# waterlevel.net
KiCad netlist of a schematic drawn in EAGLE
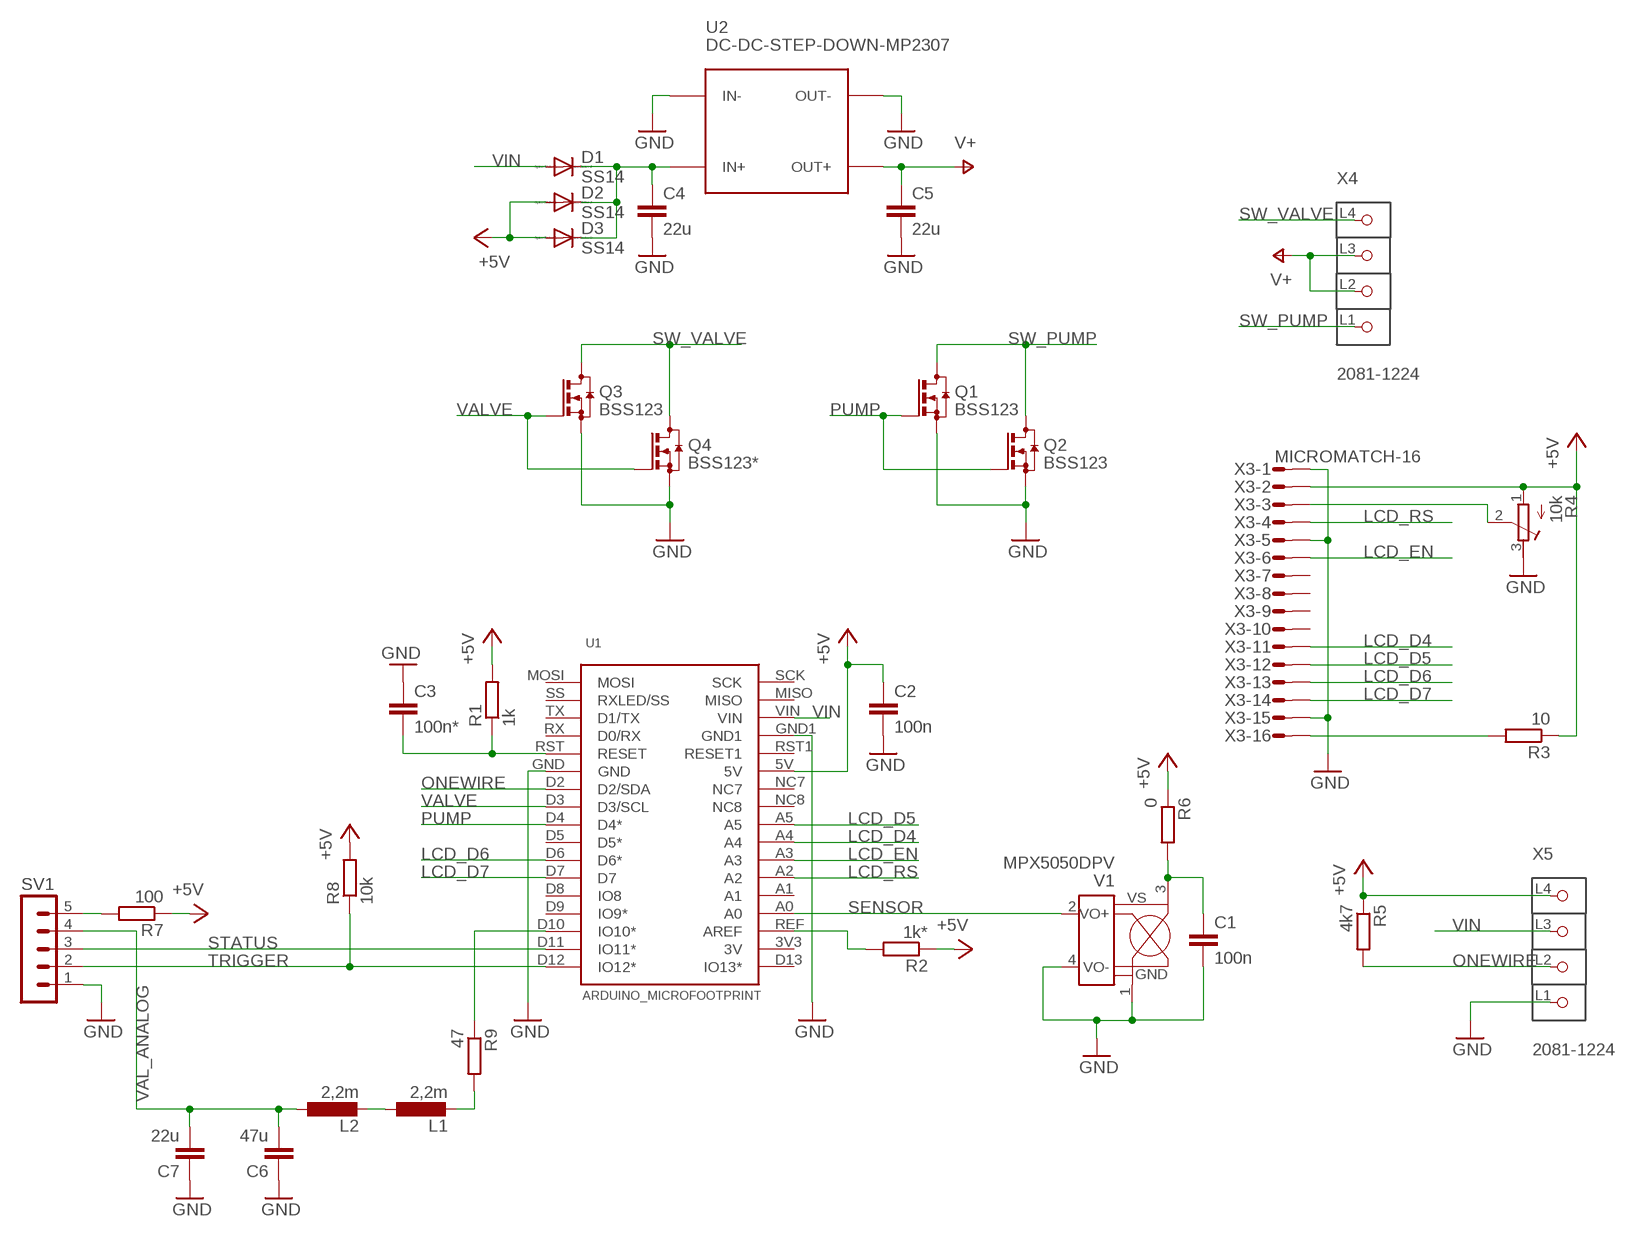
[diagram p0: schematic, sheet 1]

(export (version "E")
  (design (tool "Eeschema 10.0.6"))
  (components
    (comp (ref "C1")
      (value "100n")
      (footprint "eagle-import:C0603")
      (libsource (lib "eagle-import") (part "C-EUC0603"))
    )
    (comp (ref "C2")
      (value "100n")
      (footprint "eagle-import:C0603")
      (libsource (lib "eagle-import") (part "C-EUC0603"))
    )
    (comp (ref "C3")
      (value "100n*")
      (footprint "eagle-import:C0603")
      (libsource (lib "eagle-import") (part "C-EUC0603"))
    )
    (comp (ref "C4")
      (value "22u")
      (footprint "eagle-import:C1210K")
      (libsource (lib "eagle-import") (part "C-EUC1210K"))
    )
    (comp (ref "C5")
      (value "22u")
      (footprint "eagle-import:C1210K")
      (libsource (lib "eagle-import") (part "C-EUC1210K"))
    )
    (comp (ref "C6")
      (value "47u")
      (footprint "eagle-import:C1206K")
      (libsource (lib "eagle-import") (part "C-EUC1206K"))
    )
    (comp (ref "C7")
      (value "22u")
      (footprint "eagle-import:C1206K")
      (libsource (lib "eagle-import") (part "C-EUC1206K"))
    )
    (comp (ref "D1")
      (value "SS14")
      (footprint "eagle-import:DO214AC")
      (libsource (lib "eagle-import") (part "DIODE-DO214AC"))
    )
    (comp (ref "D2")
      (value "SS14")
      (footprint "eagle-import:DO214AC")
      (libsource (lib "eagle-import") (part "DIODE-DO214AC"))
    )
    (comp (ref "D3")
      (value "SS14")
      (footprint "eagle-import:DO214AC")
      (libsource (lib "eagle-import") (part "DIODE-DO214AC"))
    )
    (comp (ref "L1")
      (value "2,2m")
      (footprint "eagle-import:L1812")
      (libsource (lib "eagle-import") (part "L-EUL1812"))
    )
    (comp (ref "L2")
      (value "2,2m")
      (footprint "eagle-import:L1812")
      (libsource (lib "eagle-import") (part "L-EUL1812"))
    )
    (comp (ref "Q1")
      (value "BSS123")
      (footprint "eagle-import:SOT23")
      (libsource (lib "eagle-import") (part "BSS123"))
    )
    (comp (ref "Q2")
      (value "BSS123")
      (footprint "eagle-import:SOT23")
      (libsource (lib "eagle-import") (part "BSS123"))
    )
    (comp (ref "Q3")
      (value "BSS123")
      (footprint "eagle-import:SOT23")
      (libsource (lib "eagle-import") (part "BSS123"))
    )
    (comp (ref "Q4")
      (value "BSS123*")
      (footprint "eagle-import:SOT23")
      (libsource (lib "eagle-import") (part "BSS123"))
    )
    (comp (ref "R1")
      (value "1k")
      (footprint "eagle-import:R0603")
      (libsource (lib "eagle-import") (part "R-EU_R0603"))
    )
    (comp (ref "R2")
      (value "1k*")
      (footprint "eagle-import:R0603")
      (libsource (lib "eagle-import") (part "R-EU_R0603"))
    )
    (comp (ref "R3")
      (value "10")
      (footprint "eagle-import:R0603")
      (libsource (lib "eagle-import") (part "R-EU_R0603"))
    )
    (comp (ref "R4")
      (value "10k")
      (footprint "eagle-import:RTRIM64Z")
      (libsource (lib "eagle-import") (part "R-TRIMM64Z"))
    )
    (comp (ref "R5")
      (value "4k7")
      (footprint "eagle-import:R0603")
      (libsource (lib "eagle-import") (part "R-EU_R0603"))
    )
    (comp (ref "R6")
      (value "0")
      (footprint "eagle-import:R0603")
      (libsource (lib "eagle-import") (part "R-EU_R0603"))
    )
    (comp (ref "R7")
      (value "100")
      (footprint "eagle-import:R0603")
      (libsource (lib "eagle-import") (part "R-EU_R0603"))
    )
    (comp (ref "R8")
      (value "10k")
      (footprint "eagle-import:R0603")
      (libsource (lib "eagle-import") (part "R-EU_R0603"))
    )
    (comp (ref "R9")
      (value "47")
      (footprint "eagle-import:R0603")
      (libsource (lib "eagle-import") (part "R-EU_R0603"))
    )
    (comp (ref "SV1")
      (value "MA05-1")
      (footprint "eagle-import:MA05-1")
      (libsource (lib "eagle-import") (part "MA05-1"))
    )
    (comp (ref "U1")
      (value "ARDUINO_MICROFOOTPRINT")
      (footprint "eagle-import:ARDUINO-MICRO")
      (libsource (lib "eagle-import") (part "ARDUINO_MICROFOOTPRINT"))
    )
    (comp (ref "U2")
      (value "DC-DC-STEP-DOWN-MP2307")
      (footprint "eagle-import:DC-DC-STEP-DOWN-MP2307")
      (libsource (lib "eagle-import") (part "DC-DC-STEP-DOWN-MP2307"))
    )
    (comp (ref "V1")
      (value "MPX5050DPV")
      (footprint "eagle-import:MPX2050DPV")
      (fields (field (name "MF") "MOTOROLA") (field (name "MPN") "MPX2050DP"))
      (libsource (lib "eagle-import") (part "MPX2050DPV"))
    )
    (comp (ref "X3")
      (value "MICROMATCH-16")
      (footprint "eagle-import:MICROMATCH-16")
      (fields (field (name "MF") "FARNELL") (field (name "MPN") "8-215464-6"))
      (libsource (lib "eagle-import") (part "MICROMATCH-16"))
    )
    (comp (ref "X4")
      (value "2081-1224")
      (footprint "eagle-import:P-2081-1224")
      (libsource (lib "eagle-import") (part "2081-1224"))
    )
    (comp (ref "X5")
      (value "2081-1224")
      (footprint "eagle-import:P-2081-1224")
      (libsource (lib "eagle-import") (part "2081-1224"))
    )
  )
  (nets
    (net (code "1") (name "+5V") (class "Default")
      (node (ref "C2") (pin "1") (pinfunction "1_1") (pintype "passive"))
      (node (ref "D2") (pin "A") (pinfunction "A_A") (pintype "passive"))
      (node (ref "D3") (pin "A") (pinfunction "A_A") (pintype "passive"))
      (node (ref "R1") (pin "2") (pinfunction "2_2") (pintype "passive"))
      (node (ref "R2") (pin "1") (pinfunction "1_1") (pintype "passive"))
      (node (ref "R3") (pin "1") (pinfunction "1_1") (pintype "passive"))
      (node (ref "R4") (pin "1") (pinfunction "A_1") (pintype "passive"))
      (node (ref "R5") (pin "1") (pinfunction "1_1") (pintype "passive"))
      (node (ref "R6") (pin "1") (pinfunction "1_1") (pintype "passive"))
      (node (ref "R7") (pin "1") (pinfunction "1_1") (pintype "passive"))
      (node (ref "R8") (pin "2") (pinfunction "2_2") (pintype "passive"))
      (node (ref "U1") (pin "5V") (pinfunction "5V_5V") (pintype "bidirectional"))
      (node (ref "X3") (pin "2") (pinfunction "S_2") (pintype "passive"))
      (node (ref "X5") (pin "L4") (pinfunction "P4_L4") (pintype "bidirectional"))
    )
    (net (code "2") (name "/LCD_D4") (class "Default")
      (node (ref "U1") (pin "A4") (pinfunction "A4_A4") (pintype "bidirectional"))
      (node (ref "X3") (pin "11") (pinfunction "S_11") (pintype "passive"))
    )
    (net (code "3") (name "/LCD_D5") (class "Default")
      (node (ref "U1") (pin "A5") (pinfunction "A5_A5") (pintype "bidirectional"))
      (node (ref "X3") (pin "12") (pinfunction "S_12") (pintype "passive"))
    )
    (net (code "4") (name "/LCD_D6") (class "Default")
      (node (ref "U1") (pin "D6") (pinfunction "D6*_D6") (pintype "bidirectional"))
      (node (ref "X3") (pin "13") (pinfunction "S_13") (pintype "passive"))
    )
    (net (code "5") (name "/LCD_D7") (class "Default")
      (node (ref "U1") (pin "D7") (pinfunction "D7_D7") (pintype "bidirectional"))
      (node (ref "X3") (pin "14") (pinfunction "S_14") (pintype "passive"))
    )
    (net (code "6") (name "/LCD_EN") (class "Default")
      (node (ref "U1") (pin "A3") (pinfunction "A3_A3") (pintype "bidirectional"))
      (node (ref "X3") (pin "6") (pinfunction "S_6") (pintype "passive"))
    )
    (net (code "7") (name "/LCD_RS") (class "Default")
      (node (ref "U1") (pin "A2") (pinfunction "A2_A2") (pintype "bidirectional"))
      (node (ref "X3") (pin "4") (pinfunction "S_4") (pintype "passive"))
    )
    (net (code "8") (name "/ONEWIRE") (class "Default")
      (node (ref "R5") (pin "2") (pinfunction "2_2") (pintype "passive"))
      (node (ref "U1") (pin "D2") (pinfunction "D2/SDA_D2") (pintype "bidirectional"))
      (node (ref "X5") (pin "L2") (pinfunction "P2_L2") (pintype "bidirectional"))
    )
    (net (code "9") (name "/PUMP") (class "Default")
      (node (ref "Q1") (pin "1") (pinfunction "G_1") (pintype "passive"))
      (node (ref "Q2") (pin "1") (pinfunction "G_1") (pintype "passive"))
      (node (ref "U1") (pin "D4") (pinfunction "D4*_D4") (pintype "bidirectional"))
    )
    (net (code "10") (name "/SENSOR") (class "Default")
      (node (ref "U1") (pin "A0") (pinfunction "A0_A0") (pintype "bidirectional"))
      (node (ref "V1") (pin "2") (pinfunction "VO+_2") (pintype "passive"))
    )
    (net (code "11") (name "/STATUS") (class "Default")
      (node (ref "SV1") (pin "3") (pinfunction "3_3") (pintype "passive"))
      (node (ref "U1") (pin "D11") (pinfunction "IO11*_D11") (pintype "bidirectional"))
    )
    (net (code "12") (name "/SW_PUMP") (class "Default")
      (node (ref "Q1") (pin "3") (pinfunction "D_3") (pintype "passive"))
      (node (ref "Q2") (pin "3") (pinfunction "D_3") (pintype "passive"))
      (node (ref "X4") (pin "L1") (pinfunction "P1_L1") (pintype "bidirectional"))
    )
    (net (code "13") (name "/SW_VALVE") (class "Default")
      (node (ref "Q3") (pin "3") (pinfunction "D_3") (pintype "passive"))
      (node (ref "Q4") (pin "3") (pinfunction "D_3") (pintype "passive"))
      (node (ref "X4") (pin "L4") (pinfunction "P4_L4") (pintype "bidirectional"))
    )
    (net (code "14") (name "/TRIGGER") (class "Default")
      (node (ref "R8") (pin "1") (pinfunction "1_1") (pintype "passive"))
      (node (ref "SV1") (pin "2") (pinfunction "2_2") (pintype "passive"))
      (node (ref "U1") (pin "D12") (pinfunction "IO12*_D12") (pintype "bidirectional"))
    )
    (net (code "15") (name "/VALVE") (class "Default")
      (node (ref "Q3") (pin "1") (pinfunction "G_1") (pintype "passive"))
      (node (ref "Q4") (pin "1") (pinfunction "G_1") (pintype "passive"))
      (node (ref "U1") (pin "D3") (pinfunction "D3/SCL_D3") (pintype "bidirectional"))
    )
    (net (code "16") (name "/VAL_ANALOG") (class "Default")
      (node (ref "C6") (pin "2") (pinfunction "2_2") (pintype "passive"))
      (node (ref "C7") (pin "2") (pinfunction "2_2") (pintype "passive"))
      (node (ref "L2") (pin "1") (pinfunction "1_1") (pintype "passive"))
      (node (ref "SV1") (pin "4") (pinfunction "4_4") (pintype "passive"))
    )
    (net (code "17") (name "/VIN") (class "Default")
      (node (ref "D1") (pin "A") (pinfunction "A_A") (pintype "passive"))
      (node (ref "U1") (pin "VIN") (pinfunction "VIN_VIN") (pintype "bidirectional"))
      (node (ref "X5") (pin "L3") (pinfunction "P3_L3") (pintype "bidirectional"))
    )
    (net (code "18") (name "GND") (class "Default")
      (node (ref "C1") (pin "2") (pinfunction "2_2") (pintype "passive"))
      (node (ref "C2") (pin "2") (pinfunction "2_2") (pintype "passive"))
      (node (ref "C3") (pin "1") (pinfunction "1_1") (pintype "passive"))
      (node (ref "C4") (pin "2") (pinfunction "2_2") (pintype "passive"))
      (node (ref "C5") (pin "2") (pinfunction "2_2") (pintype "passive"))
      (node (ref "C6") (pin "1") (pinfunction "1_1") (pintype "passive"))
      (node (ref "C7") (pin "1") (pinfunction "1_1") (pintype "passive"))
      (node (ref "Q1") (pin "2") (pinfunction "S_2") (pintype "passive"))
      (node (ref "Q2") (pin "2") (pinfunction "S_2") (pintype "passive"))
      (node (ref "Q3") (pin "2") (pinfunction "S_2") (pintype "passive"))
      (node (ref "Q4") (pin "2") (pinfunction "S_2") (pintype "passive"))
      (node (ref "R4") (pin "3") (pinfunction "E_3") (pintype "passive"))
      (node (ref "SV1") (pin "1") (pinfunction "1_1") (pintype "passive"))
      (node (ref "U1") (pin "GND") (pinfunction "GND_GND") (pintype "bidirectional"))
      (node (ref "U1") (pin "GND1") (pinfunction "GND1_GND1") (pintype "bidirectional"))
      (node (ref "U2") (pin "IN-") (pinfunction "IN-_IN-") (pintype "bidirectional"))
      (node (ref "U2") (pin "OUT-") (pinfunction "OUT-_OUT-") (pintype "bidirectional"))
      (node (ref "V1") (pin "1") (pinfunction "GND_1") (pintype "passive"))
      (node (ref "V1") (pin "4") (pinfunction "VO-_4") (pintype "passive"))
      (node (ref "X3") (pin "1") (pinfunction "S_1") (pintype "passive"))
      (node (ref "X3") (pin "15") (pinfunction "S_15") (pintype "passive"))
      (node (ref "X3") (pin "5") (pinfunction "S_5") (pintype "passive"))
      (node (ref "X5") (pin "L1") (pinfunction "P1_L1") (pintype "bidirectional"))
    )
    (net (code "19") (name "Net-(C4-Pad1)") (class "Default")
      (node (ref "C4") (pin "1") (pinfunction "1_1") (pintype "passive"))
      (node (ref "D1") (pin "C") (pinfunction "C_C") (pintype "passive"))
      (node (ref "D2") (pin "C") (pinfunction "C_C") (pintype "passive"))
      (node (ref "D3") (pin "C") (pinfunction "C_C") (pintype "passive"))
      (node (ref "U2") (pin "IN+") (pinfunction "IN+_IN+") (pintype "bidirectional"))
    )
    (net (code "20") (name "Net-(L1-Pad1)") (class "Default")
      (node (ref "L1") (pin "1") (pinfunction "1_1") (pintype "passive"))
      (node (ref "L2") (pin "2") (pinfunction "2_2") (pintype "passive"))
    )
    (net (code "21") (name "Net-(L1-Pad2)") (class "Default")
      (node (ref "L1") (pin "2") (pinfunction "2_2") (pintype "passive"))
      (node (ref "R9") (pin "2") (pinfunction "2_2") (pintype "passive"))
    )
    (net (code "22") (name "Net-(R4-S)") (class "Default")
      (node (ref "R4") (pin "2") (pinfunction "S_2") (pintype "passive"))
      (node (ref "X3") (pin "3") (pinfunction "S_3") (pintype "passive"))
    )
    (net (code "23") (name "Net-(R7-Pad2)") (class "Default")
      (node (ref "R7") (pin "2") (pinfunction "2_2") (pintype "passive"))
      (node (ref "SV1") (pin "5") (pinfunction "5_5") (pintype "passive"))
    )
    (net (code "24") (name "Net-(U1-AREF)") (class "Default")
      (node (ref "R2") (pin "2") (pinfunction "2_2") (pintype "passive"))
      (node (ref "U1") (pin "REF") (pinfunction "AREF_REF") (pintype "bidirectional"))
    )
    (net (code "25") (name "Net-(U1-IO10*)") (class "Default")
      (node (ref "R9") (pin "1") (pinfunction "1_1") (pintype "passive"))
      (node (ref "U1") (pin "D10") (pinfunction "IO10*_D10") (pintype "bidirectional"))
    )
    (net (code "26") (name "Net-(U1-RESET)") (class "Default")
      (node (ref "C3") (pin "2") (pinfunction "2_2") (pintype "passive"))
      (node (ref "R1") (pin "1") (pinfunction "1_1") (pintype "passive"))
      (node (ref "U1") (pin "RST") (pinfunction "RESET_RST") (pintype "bidirectional"))
    )
    (net (code "27") (name "Net-(V1-VS)") (class "Default")
      (node (ref "C1") (pin "1") (pinfunction "1_1") (pintype "passive"))
      (node (ref "R6") (pin "2") (pinfunction "2_2") (pintype "passive"))
      (node (ref "V1") (pin "3") (pinfunction "VS_3") (pintype "passive"))
    )
    (net (code "28") (name "Net-(X3H-S)") (class "Default")
      (node (ref "R3") (pin "2") (pinfunction "2_2") (pintype "passive"))
      (node (ref "X3") (pin "16") (pinfunction "S_16") (pintype "passive"))
    )
    (net (code "29") (name "V+") (class "Default")
      (node (ref "C5") (pin "1") (pinfunction "1_1") (pintype "passive"))
      (node (ref "U2") (pin "OUT+") (pinfunction "OUT+_OUT+") (pintype "bidirectional"))
      (node (ref "X4") (pin "L2") (pinfunction "P2_L2") (pintype "bidirectional"))
      (node (ref "X4") (pin "L3") (pinfunction "P3_L3") (pintype "bidirectional"))
    )
    (net (code "30") (name "unconnected-(U1-3V-Pad3V3)") (class "Default")
      (node (ref "U1") (pin "3V3") (pinfunction "3V_3V3") (pintype "bidirectional"))
    )
    (net (code "31") (name "unconnected-(U1-D0{slash}RX-PadRX)") (class "Default")
      (node (ref "U1") (pin "RX") (pinfunction "D0/RX_RX") (pintype "bidirectional"))
    )
    (net (code "32") (name "unconnected-(U1-D1{slash}TX-PadTX)") (class "Default")
      (node (ref "U1") (pin "TX") (pinfunction "D1/TX_TX") (pintype "bidirectional"))
    )
    (net (code "33") (name "unconnected-(U1-D5*-PadD5)") (class "Default")
      (node (ref "U1") (pin "D5") (pinfunction "D5*_D5") (pintype "bidirectional"))
    )
    (net (code "34") (name "unconnected-(U1-IO8-PadD8)") (class "Default")
      (node (ref "U1") (pin "D8") (pinfunction "IO8_D8") (pintype "bidirectional"))
    )
    (net (code "35") (name "unconnected-(U1-IO9*-PadD9)") (class "Default")
      (node (ref "U1") (pin "D9") (pinfunction "IO9*_D9") (pintype "bidirectional"))
    )
    (net (code "36") (name "unconnected-(U1-IO13*-PadD13)") (class "Default")
      (node (ref "U1") (pin "D13") (pinfunction "IO13*_D13") (pintype "bidirectional"))
    )
    (net (code "37") (name "unconnected-(U1-PadA1)") (class "Default")
      (node (ref "U1") (pin "A1") (pinfunction "A1_A1") (pintype "bidirectional"))
    )
    (net (code "38") (name "unconnected-(U1-PadMISO)") (class "Default")
      (node (ref "U1") (pin "MISO") (pinfunction "MISO_MISO") (pintype "bidirectional"))
    )
    (net (code "39") (name "unconnected-(U1-PadMOSI)") (class "Default")
      (node (ref "U1") (pin "MOSI") (pinfunction "MOSI_MOSI") (pintype "bidirectional"))
    )
    (net (code "40") (name "unconnected-(U1-PadNC7)") (class "Default")
      (node (ref "U1") (pin "NC7") (pinfunction "NC7_NC7") (pintype "bidirectional"))
    )
    (net (code "41") (name "unconnected-(U1-PadNC8)") (class "Default")
      (node (ref "U1") (pin "NC8") (pinfunction "NC8_NC8") (pintype "bidirectional"))
    )
    (net (code "42") (name "unconnected-(U1-PadSCK)") (class "Default")
      (node (ref "U1") (pin "SCK") (pinfunction "SCK_SCK") (pintype "bidirectional"))
    )
    (net (code "43") (name "unconnected-(U1-RESET1-PadRST1)") (class "Default")
      (node (ref "U1") (pin "RST1") (pinfunction "RESET1_RST1") (pintype "bidirectional"))
    )
    (net (code "44") (name "unconnected-(U1-RXLED{slash}SS-PadSS)") (class "Default")
      (node (ref "U1") (pin "SS") (pinfunction "RXLED/SS_SS") (pintype "bidirectional"))
    )
    (net (code "45") (name "unconnected-(X3B-S-Pad10)") (class "Default")
      (node (ref "X3") (pin "10") (pinfunction "S_10") (pintype "passive"))
    )
    (net (code "46") (name "unconnected-(X3N-S-Pad7)") (class "Default")
      (node (ref "X3") (pin "7") (pinfunction "S_7") (pintype "passive"))
    )
    (net (code "47") (name "unconnected-(X3O-S-Pad8)") (class "Default")
      (node (ref "X3") (pin "8") (pinfunction "S_8") (pintype "passive"))
    )
    (net (code "48") (name "unconnected-(X3P-S-Pad9)") (class "Default")
      (node (ref "X3") (pin "9") (pinfunction "S_9") (pintype "passive"))
    )
  )
)
